# PowerB.net
KiCad netlist of a schematic drawn in Altium Designer
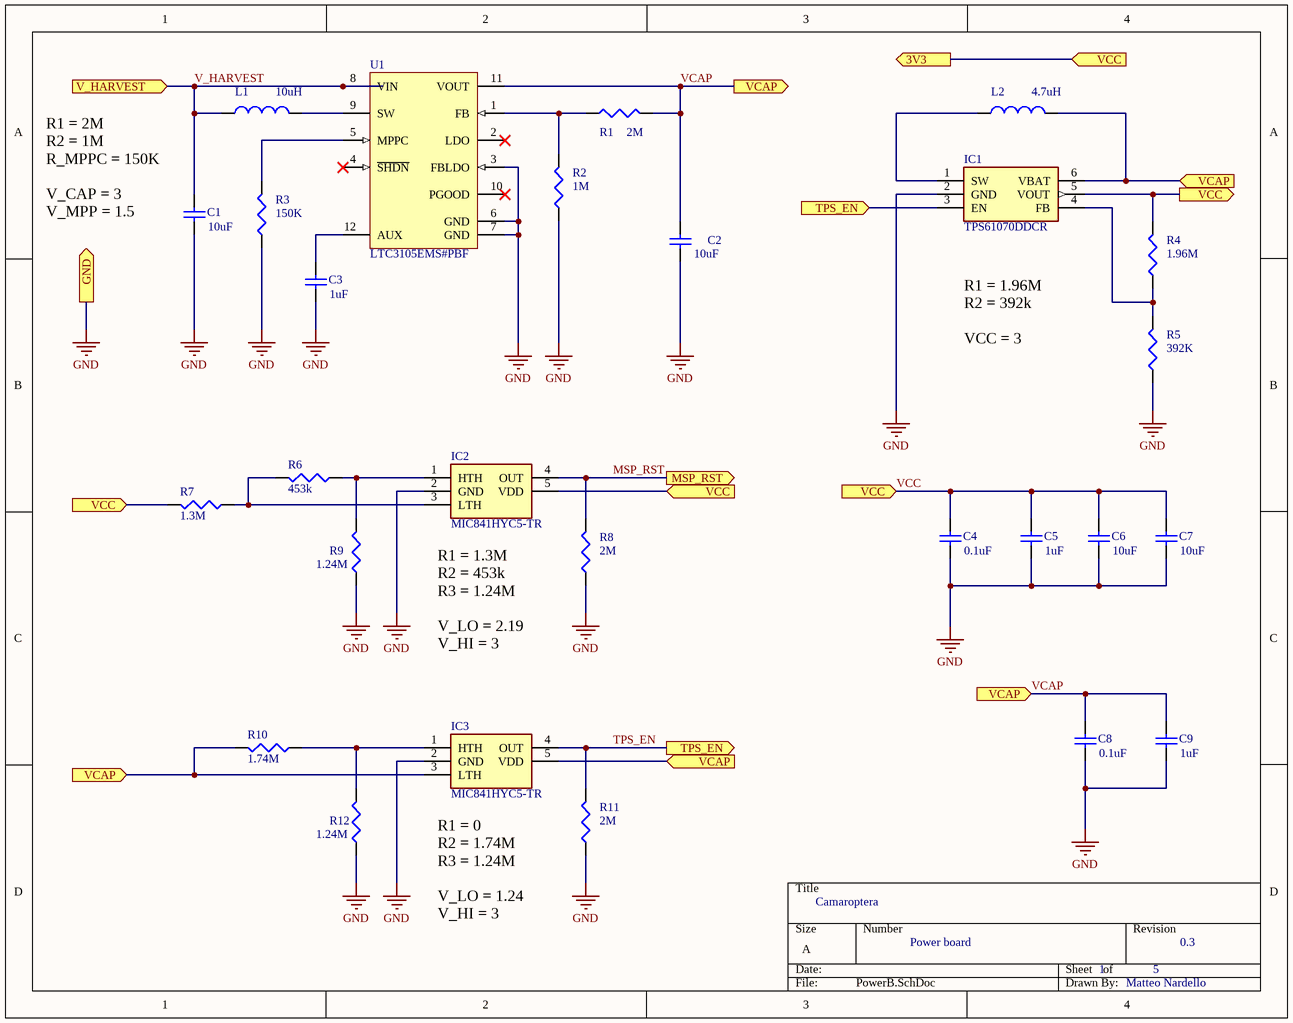
[diagram p0: PowerB.SchDoc]

(export (version "E")
  (design (tool "Eeschema 10.0.6"))
  (components
    (comp (ref "C1")
      (value "10uF")
      (footprint "1608[0603]")
      (description "CAP CER 6.3V X5R/X7R 0603")
      (fields (field (name "Comment") "Cap") (field (name "PUBLISHER") "Altium Limited"))
      (libsource (lib "Miscellaneous Devices") (part "Cap"))
    )
    (comp (ref "C2")
      (value "10uF")
      (footprint "1608[0603]")
      (description "CAP CER 6.3V X5R/X7R 0603")
      (fields (field (name "Comment") "Cap") (field (name "PUBLISHER") "Altium Limited"))
      (libsource (lib "Miscellaneous Devices") (part "Cap"))
    )
    (comp (ref "C3")
      (value "1uF")
      (footprint "1608[0603]")
      (description "CAP CER 6.3V X5R/X7R 0603")
      (fields (field (name "Comment") "Cap") (field (name "PUBLISHER") "Altium Limited"))
      (libsource (lib "Miscellaneous Devices") (part "Cap"))
    )
    (comp (ref "C4")
      (value "0.1uF")
      (footprint "1608[0603]")
      (description "CAP CER 6.3V X5R/X7R 0603")
      (fields (field (name "Comment") "Cap") (field (name "PUBLISHER") "Altium Limited"))
      (libsource (lib "Miscellaneous Devices") (part "Cap"))
    )
    (comp (ref "C5")
      (value "1uF")
      (footprint "1608[0603]")
      (description "CAP CER 6.3V X5R/X7R 0603")
      (fields (field (name "Comment") "Cap") (field (name "PUBLISHER") "Altium Limited"))
      (libsource (lib "Miscellaneous Devices") (part "Cap"))
    )
    (comp (ref "C6")
      (value "10uF")
      (footprint "1608[0603]")
      (description "CAP CER 6.3V X5R/X7R 0603")
      (fields (field (name "Comment") "Cap") (field (name "PUBLISHER") "Altium Limited"))
      (libsource (lib "Miscellaneous Devices") (part "Cap"))
    )
    (comp (ref "C7")
      (value "10uF")
      (footprint "1608[0603]")
      (description "CAP CER 6.3V X5R/X7R 0603")
      (fields (field (name "Comment") "Cap") (field (name "PUBLISHER") "Altium Limited"))
      (libsource (lib "Miscellaneous Devices") (part "Cap"))
    )
    (comp (ref "C8")
      (value "0.1uF")
      (footprint "1608[0603]")
      (description "CAP CER 6.3V X5R/X7R 0603")
      (fields (field (name "Comment") "Cap") (field (name "PUBLISHER") "Altium Limited"))
      (libsource (lib "Miscellaneous Devices") (part "Cap"))
    )
    (comp (ref "C9")
      (value "1uF")
      (footprint "1608[0603]")
      (description "CAP CER 6.3V X5R/X7R 0603")
      (fields (field (name "Comment") "Cap") (field (name "PUBLISHER") "Altium Limited"))
      (libsource (lib "Miscellaneous Devices") (part "Cap"))
    )
    (comp (ref "IC1")
      (value "TPS61070DDCR")
      (footprint "SamacSys:SOT95P280X110-6N")
      (description "90% Efficient Synchronous Boost Converter With 600-mA Switch")
      (fields (field (name "MOUSER PART NUMBER") "595-TPS61070DDCR"))
      (libsource (lib "*") (part "TPS61070DDCR"))
    )
    (comp (ref "IC2")
      (value "MIC841HYC5-TR")
      (footprint "SamacSys:SOT65P210X110-5N")
      (description "Comparator with 1.25% Reference and Adjustable Hysteresis")
      (fields
        (field (name "MOUSER PART NUMBER") "998-MIC841HYC5TR")
        (field (name "RS PART NUMBER") "1654292")
      )
      (libsource (lib "*") (part "MIC841HYC5-TR"))
    )
    (comp (ref "IC3")
      (value "MIC841HYC5-TR")
      (footprint "SamacSys:SOT65P210X110-5N")
      (description "Comparator with 1.25% Reference and Adjustable Hysteresis")
      (fields
        (field (name "MOUSER PART NUMBER") "998-MIC841HYC5TR")
        (field (name "RS PART NUMBER") "1654292")
      )
      (libsource (lib "*") (part "MIC841HYC5-TR"))
    )
    (comp (ref "L1")
      (value "10uH")
      (footprint "C1210")
      (description "Inductor")
      (fields (field (name "PART") "CBC3225T100KR") (field (name "PUBLISHER") "Altium Limited"))
      (libsource (lib "Miscellaneous Devices") (part "Inductor"))
    )
    (comp (ref "L2")
      (value "4.7uH")
      (footprint "C1210")
      (description "Inductor")
      (fields (field (name "PART") "CBC3225T4R7MR") (field (name "PUBLISHER") "Altium Limited"))
      (libsource (lib "Miscellaneous Devices") (part "Inductor"))
    )
    (comp (ref "R1")
      (value "2M")
      (footprint "1608[0603]")
      (description "RES 1/10W 1% 0603 SMD")
      (fields (field (name "Comment") "Res3") (field (name "PUBLISHER") "Altium Limited"))
      (libsource (lib "Miscellaneous Devices") (part "Res3"))
    )
    (comp (ref "R2")
      (value "1M")
      (footprint "1608[0603]")
      (description "RES 1/10W 1% 0603 SMD")
      (fields (field (name "Comment") "Res3") (field (name "PUBLISHER") "Altium Limited"))
      (libsource (lib "Miscellaneous Devices") (part "Res3"))
    )
    (comp (ref "R3")
      (value "150K")
      (footprint "1608[0603]")
      (description "RES 1/10W 1% 0603 SMD")
      (fields (field (name "Comment") "Res3") (field (name "PUBLISHER") "Altium Limited"))
      (libsource (lib "Miscellaneous Devices") (part "Res3"))
    )
    (comp (ref "R4")
      (value "1.96M")
      (footprint "1608[0603]")
      (description "RES 1/10W 1% 0603 SMD")
      (fields (field (name "Comment") "Res3") (field (name "PUBLISHER") "Altium Limited"))
      (libsource (lib "Miscellaneous Devices") (part "Res3"))
    )
    (comp (ref "R5")
      (value "392K")
      (footprint "1608[0603]")
      (description "RES 1/10W 1% 0603 SMD")
      (fields (field (name "Comment") "Res3") (field (name "PUBLISHER") "Altium Limited"))
      (libsource (lib "Miscellaneous Devices") (part "Res3"))
    )
    (comp (ref "R6")
      (value "453k")
      (footprint "1608[0603]")
      (description "RES 1/10W 1% 0603 SMD")
      (fields (field (name "Comment") "Res3") (field (name "PUBLISHER") "Altium Limited"))
      (libsource (lib "Miscellaneous Devices") (part "Res3"))
    )
    (comp (ref "R7")
      (value "1.3M")
      (footprint "1608[0603]")
      (description "RES 1/10W 1% 0603 SMD")
      (fields (field (name "Comment") "Res3") (field (name "PUBLISHER") "Altium Limited"))
      (libsource (lib "Miscellaneous Devices") (part "Res3"))
    )
    (comp (ref "R8")
      (value "2M")
      (footprint "1608[0603]")
      (description "RES 1/10W 1% 0603 SMD")
      (fields (field (name "Comment") "Res3") (field (name "PUBLISHER") "Altium Limited"))
      (libsource (lib "Miscellaneous Devices") (part "Res3"))
    )
    (comp (ref "R9")
      (value "1.24M")
      (footprint "1608[0603]")
      (description "RES 1/10W 1% 0603 SMD")
      (fields (field (name "Comment") "Res3") (field (name "PUBLISHER") "Altium Limited"))
      (libsource (lib "Miscellaneous Devices") (part "Res3"))
    )
    (comp (ref "R10")
      (value "1.74M")
      (footprint "1608[0603]")
      (description "RES 1/10W 1% 0603 SMD")
      (fields (field (name "Comment") "Res3") (field (name "PUBLISHER") "Altium Limited"))
      (libsource (lib "Miscellaneous Devices") (part "Res3"))
    )
    (comp (ref "R11")
      (value "2M")
      (footprint "1608[0603]")
      (description "RES 1/10W 1% 0603 SMD")
      (fields (field (name "Comment") "Res3") (field (name "PUBLISHER") "Altium Limited"))
      (libsource (lib "Miscellaneous Devices") (part "Res3"))
    )
    (comp (ref "R12")
      (value "1.24M")
      (footprint "1608[0603]")
      (description "RES 1/10W 1% 0603 SMD")
      (fields (field (name "Comment") "Res3") (field (name "PUBLISHER") "Altium Limited"))
      (libsource (lib "Miscellaneous Devices") (part "Res3"))
    )
    (comp (ref "U1")
      (value "LTC3105EMS#PBF")
      (footprint "LT-MS-12_N")
      (fields (field (name "MANUFACTURER") "Linear Technology"))
      (libsource (lib "Altium Content Vault") (part "LT-LTC3105-MS-12"))
    )
  )
  (nets
    (net (code "1") (name "/MSP_RST") (class "Default")
      (node (ref "IC2") (pin "4") (pinfunction "OUT_4") (pintype "passive"))
      (node (ref "R8") (pin "2") (pinfunction "2_2") (pintype "passive"))
    )
    (net (code "2") (name "/TPS_EN") (class "Default")
      (node (ref "IC1") (pin "3") (pinfunction "EN_3") (pintype "passive"))
      (node (ref "IC3") (pin "4") (pinfunction "OUT_4") (pintype "passive"))
      (node (ref "R11") (pin "2") (pinfunction "2_2") (pintype "passive"))
    )
    (net (code "3") (name "/VCAP") (class "Default")
      (node (ref "C2") (pin "2") (pinfunction "2_2") (pintype "passive"))
      (node (ref "C8") (pin "2") (pinfunction "2_2") (pintype "passive"))
      (node (ref "C9") (pin "2") (pinfunction "2_2") (pintype "passive"))
      (node (ref "IC1") (pin "6") (pinfunction "VBAT_6") (pintype "passive"))
      (node (ref "IC3") (pin "3") (pinfunction "LTH_3") (pintype "passive"))
      (node (ref "IC3") (pin "5") (pinfunction "VDD_5") (pintype "passive"))
      (node (ref "L2") (pin "2") (pinfunction "2_2") (pintype "passive"))
      (node (ref "R1") (pin "2") (pinfunction "2_2") (pintype "passive"))
      (node (ref "R10") (pin "2") (pinfunction "2_2") (pintype "passive"))
      (node (ref "U1") (pin "11") (pinfunction "VOUT_11") (pintype "power_in"))
    )
    (net (code "4") (name "/VCC") (class "Default")
      (node (ref "C4") (pin "2") (pinfunction "2_2") (pintype "passive"))
      (node (ref "C5") (pin "2") (pinfunction "2_2") (pintype "passive"))
      (node (ref "C6") (pin "2") (pinfunction "2_2") (pintype "passive"))
      (node (ref "C7") (pin "2") (pinfunction "2_2") (pintype "passive"))
      (node (ref "IC1") (pin "5") (pinfunction "VOUT_5") (pintype "output"))
      (node (ref "IC2") (pin "5") (pinfunction "VDD_5") (pintype "passive"))
      (node (ref "R4") (pin "2") (pinfunction "2_2") (pintype "passive"))
      (node (ref "R7") (pin "2") (pinfunction "2_2") (pintype "passive"))
    )
    (net (code "5") (name "/V_HARVEST") (class "Default")
      (node (ref "C1") (pin "2") (pinfunction "2_2") (pintype "passive"))
      (node (ref "L1") (pin "1") (pinfunction "1_1") (pintype "passive"))
      (node (ref "U1") (pin "8") (pinfunction "VIN_8") (pintype "power_in"))
    )
    (net (code "6") (name "GND") (class "Default")
      (node (ref "C1") (pin "1") (pinfunction "1_1") (pintype "passive"))
      (node (ref "C2") (pin "1") (pinfunction "1_1") (pintype "passive"))
      (node (ref "C3") (pin "1") (pinfunction "1_1") (pintype "passive"))
      (node (ref "C4") (pin "1") (pinfunction "1_1") (pintype "passive"))
      (node (ref "C5") (pin "1") (pinfunction "1_1") (pintype "passive"))
      (node (ref "C6") (pin "1") (pinfunction "1_1") (pintype "passive"))
      (node (ref "C7") (pin "1") (pinfunction "1_1") (pintype "passive"))
      (node (ref "C8") (pin "1") (pinfunction "1_1") (pintype "passive"))
      (node (ref "C9") (pin "1") (pinfunction "1_1") (pintype "passive"))
      (node (ref "IC1") (pin "2") (pinfunction "GND_2") (pintype "power_in"))
      (node (ref "IC2") (pin "2") (pinfunction "GND_2") (pintype "passive"))
      (node (ref "IC3") (pin "2") (pinfunction "GND_2") (pintype "passive"))
      (node (ref "R11") (pin "1") (pinfunction "1_1") (pintype "passive"))
      (node (ref "R12") (pin "1") (pinfunction "1_1") (pintype "passive"))
      (node (ref "R2") (pin "1") (pinfunction "1_1") (pintype "passive"))
      (node (ref "R3") (pin "1") (pinfunction "1_1") (pintype "passive"))
      (node (ref "R5") (pin "1") (pinfunction "1_1") (pintype "passive"))
      (node (ref "R8") (pin "1") (pinfunction "1_1") (pintype "passive"))
      (node (ref "R9") (pin "1") (pinfunction "1_1") (pintype "passive"))
      (node (ref "U1") (pin "3") (pinfunction "FBLDO_3") (pintype "input"))
      (node (ref "U1") (pin "6") (pinfunction "GND_6") (pintype "power_in"))
      (node (ref "U1") (pin "7") (pinfunction "GND_7") (pintype "power_in"))
    )
    (net (code "7") (name "Net-(IC1-FB)") (class "Default")
      (node (ref "IC1") (pin "4") (pinfunction "FB_4") (pintype "passive"))
      (node (ref "R4") (pin "1") (pinfunction "1_1") (pintype "passive"))
      (node (ref "R5") (pin "2") (pinfunction "2_2") (pintype "passive"))
    )
    (net (code "8") (name "Net-(IC1-SW)") (class "Default")
      (node (ref "IC1") (pin "1") (pinfunction "SW_1") (pintype "passive"))
      (node (ref "L2") (pin "1") (pinfunction "1_1") (pintype "passive"))
    )
    (net (code "9") (name "Net-(IC2-HTH)") (class "Default")
      (node (ref "IC2") (pin "1") (pinfunction "HTH_1") (pintype "passive"))
      (node (ref "R6") (pin "1") (pinfunction "1_1") (pintype "passive"))
      (node (ref "R9") (pin "2") (pinfunction "2_2") (pintype "passive"))
    )
    (net (code "10") (name "Net-(IC2-LTH)") (class "Default")
      (node (ref "IC2") (pin "3") (pinfunction "LTH_3") (pintype "passive"))
      (node (ref "R6") (pin "2") (pinfunction "2_2") (pintype "passive"))
      (node (ref "R7") (pin "1") (pinfunction "1_1") (pintype "passive"))
    )
    (net (code "11") (name "Net-(IC3-HTH)") (class "Default")
      (node (ref "IC3") (pin "1") (pinfunction "HTH_1") (pintype "passive"))
      (node (ref "R10") (pin "1") (pinfunction "1_1") (pintype "passive"))
      (node (ref "R12") (pin "2") (pinfunction "2_2") (pintype "passive"))
    )
    (net (code "12") (name "Net-(U1-AUX)") (class "Default")
      (node (ref "C3") (pin "2") (pinfunction "2_2") (pintype "passive"))
      (node (ref "U1") (pin "12") (pinfunction "AUX_12") (pintype "power_in"))
    )
    (net (code "13") (name "Net-(U1-FB)") (class "Default")
      (node (ref "R1") (pin "1") (pinfunction "1_1") (pintype "passive"))
      (node (ref "R2") (pin "2") (pinfunction "2_2") (pintype "passive"))
      (node (ref "U1") (pin "1") (pinfunction "FB_1") (pintype "input"))
    )
    (net (code "14") (name "Net-(U1-MPPC)") (class "Default")
      (node (ref "R3") (pin "2") (pinfunction "2_2") (pintype "passive"))
      (node (ref "U1") (pin "5") (pinfunction "MPPC_5") (pintype "input"))
    )
    (net (code "15") (name "Net-(U1-SW)") (class "Default")
      (node (ref "L1") (pin "2") (pinfunction "2_2") (pintype "passive"))
      (node (ref "U1") (pin "9") (pinfunction "SW_9") (pintype "power_in"))
    )
    (net (code "16") (name "unconnected-(U1-LDO-Pad2)") (class "Default")
      (node (ref "U1") (pin "2") (pinfunction "LDO_2") (pintype "power_in+no_connect"))
    )
    (net (code "17") (name "unconnected-(U1-PGOOD-Pad10)") (class "Default")
      (node (ref "U1") (pin "10") (pinfunction "PGOOD_10") (pintype "open_collector+no_connect"))
    )
    (net (code "18") (name "unconnected-(U1-~{SHDN}-Pad4)") (class "Default")
      (node (ref "U1") (pin "4") (pinfunction "~{SHDN}_4") (pintype "input+no_connect"))
    )
  )
)
